# Sheet1.net
KiCad netlist of a schematic drawn in Altium Designer
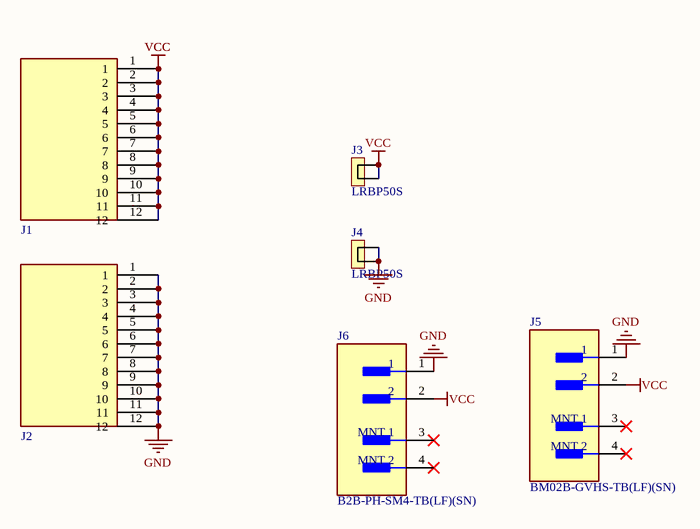
[diagram p0: Sheet1.SchDoc]

(export (version "E")
  (design (tool "Eeschema 10.0.6"))
  (components
    (comp (ref "J1")
      (value "A01F-H1-A Female")
      (footprint "A01F-H1-A")
      (libsource (lib "Schlib") (part "A01F-H1-A"))
    )
    (comp (ref "J2")
      (value "A01F-H1-A Female")
      (footprint "A01F-H1-A")
      (libsource (lib "Schlib") (part "A01F-H1-A"))
    )
    (comp (ref "J3") (value "LRBP50S") (footprint "LRBP50S") (libsource (lib "Schlib") (part "LRBP50S")))
    (comp (ref "J4") (value "LRBP50S") (footprint "LRBP50S") (libsource (lib "Schlib") (part "LRBP50S")))
    (comp (ref "J5")
      (value "BM02B-GVHS-TB(LF)(SN)")
      (footprint "FP-BM02B-GVHS-TB_LF_SN-MFG")
      (description "CONN HEADER SMD 2POS 1.25MM")
      (libsource (lib "Altium Content Vault") (part "56ec3178a87b3978bdc1b3682cd516a"))
    )
    (comp (ref "J6")
      (value "B2B-PH-SM4-TB(LF)(SN)")
      (footprint "FP-B2B-PH-SM4-TB_LF_SN-MFG")
      (description "CONN HEADER SMD 2POS 2MM")
      (libsource (lib "Altium Content Vault") (part "56ec3178a87b3978bdc1b3682cd516a"))
    )
  )
  (nets
    (net (code "1") (name "GND") (class "Default")
      (node (ref "J2") (pin "1") (pinfunction "1_1") (pintype "passive"))
      (node (ref "J2") (pin "10") (pinfunction "10_10") (pintype "passive"))
      (node (ref "J2") (pin "11") (pinfunction "11_11") (pintype "passive"))
      (node (ref "J2") (pin "12") (pinfunction "12_12") (pintype "passive"))
      (node (ref "J2") (pin "2") (pinfunction "2_2") (pintype "passive"))
      (node (ref "J2") (pin "3") (pinfunction "3_3") (pintype "passive"))
      (node (ref "J2") (pin "4") (pinfunction "4_4") (pintype "passive"))
      (node (ref "J2") (pin "5") (pinfunction "5_5") (pintype "passive"))
      (node (ref "J2") (pin "6") (pinfunction "6_6") (pintype "passive"))
      (node (ref "J2") (pin "7") (pinfunction "7_7") (pintype "passive"))
      (node (ref "J2") (pin "8") (pinfunction "8_8") (pintype "passive"))
      (node (ref "J2") (pin "9") (pinfunction "9_9") (pintype "passive"))
      (node (ref "J4") (pin "1") (pinfunction "1_1") (pintype "passive"))
      (node (ref "J4") (pin "2") (pinfunction "2_2") (pintype "passive"))
      (node (ref "J5") (pin "1") (pinfunction "1_1") (pintype "passive"))
      (node (ref "J6") (pin "1") (pinfunction "1_1") (pintype "passive"))
    )
    (net (code "2") (name "VCC") (class "Default")
      (node (ref "J1") (pin "1") (pinfunction "1_1") (pintype "passive"))
      (node (ref "J1") (pin "10") (pinfunction "10_10") (pintype "passive"))
      (node (ref "J1") (pin "11") (pinfunction "11_11") (pintype "passive"))
      (node (ref "J1") (pin "12") (pinfunction "12_12") (pintype "passive"))
      (node (ref "J1") (pin "2") (pinfunction "2_2") (pintype "passive"))
      (node (ref "J1") (pin "3") (pinfunction "3_3") (pintype "passive"))
      (node (ref "J1") (pin "4") (pinfunction "4_4") (pintype "passive"))
      (node (ref "J1") (pin "5") (pinfunction "5_5") (pintype "passive"))
      (node (ref "J1") (pin "6") (pinfunction "6_6") (pintype "passive"))
      (node (ref "J1") (pin "7") (pinfunction "7_7") (pintype "passive"))
      (node (ref "J1") (pin "8") (pinfunction "8_8") (pintype "passive"))
      (node (ref "J1") (pin "9") (pinfunction "9_9") (pintype "passive"))
      (node (ref "J3") (pin "1") (pinfunction "1_1") (pintype "passive"))
      (node (ref "J3") (pin "2") (pinfunction "2_2") (pintype "passive"))
      (node (ref "J5") (pin "2") (pinfunction "2_2") (pintype "passive"))
      (node (ref "J6") (pin "2") (pinfunction "2_2") (pintype "passive"))
    )
    (net (code "3") (name "unconnected-(J5-MNT_1-Pad3)") (class "Default")
      (node (ref "J5") (pin "3") (pinfunction "MNT_1_3") (pintype "passive+no_connect"))
    )
    (net (code "4") (name "unconnected-(J5-MNT_2-Pad4)") (class "Default")
      (node (ref "J5") (pin "4") (pinfunction "MNT_2_4") (pintype "passive+no_connect"))
    )
    (net (code "5") (name "unconnected-(J6-MNT_1-Pad3)") (class "Default")
      (node (ref "J6") (pin "3") (pinfunction "MNT_1_3") (pintype "passive+no_connect"))
    )
    (net (code "6") (name "unconnected-(J6-MNT_2-Pad4)") (class "Default")
      (node (ref "J6") (pin "4") (pinfunction "MNT_2_4") (pintype "passive+no_connect"))
    )
  )
)
